# SMC_FrontPanel_ExtensionBoard_Step2_V12_.net
KiCad netlist of a schematic drawn in EAGLE
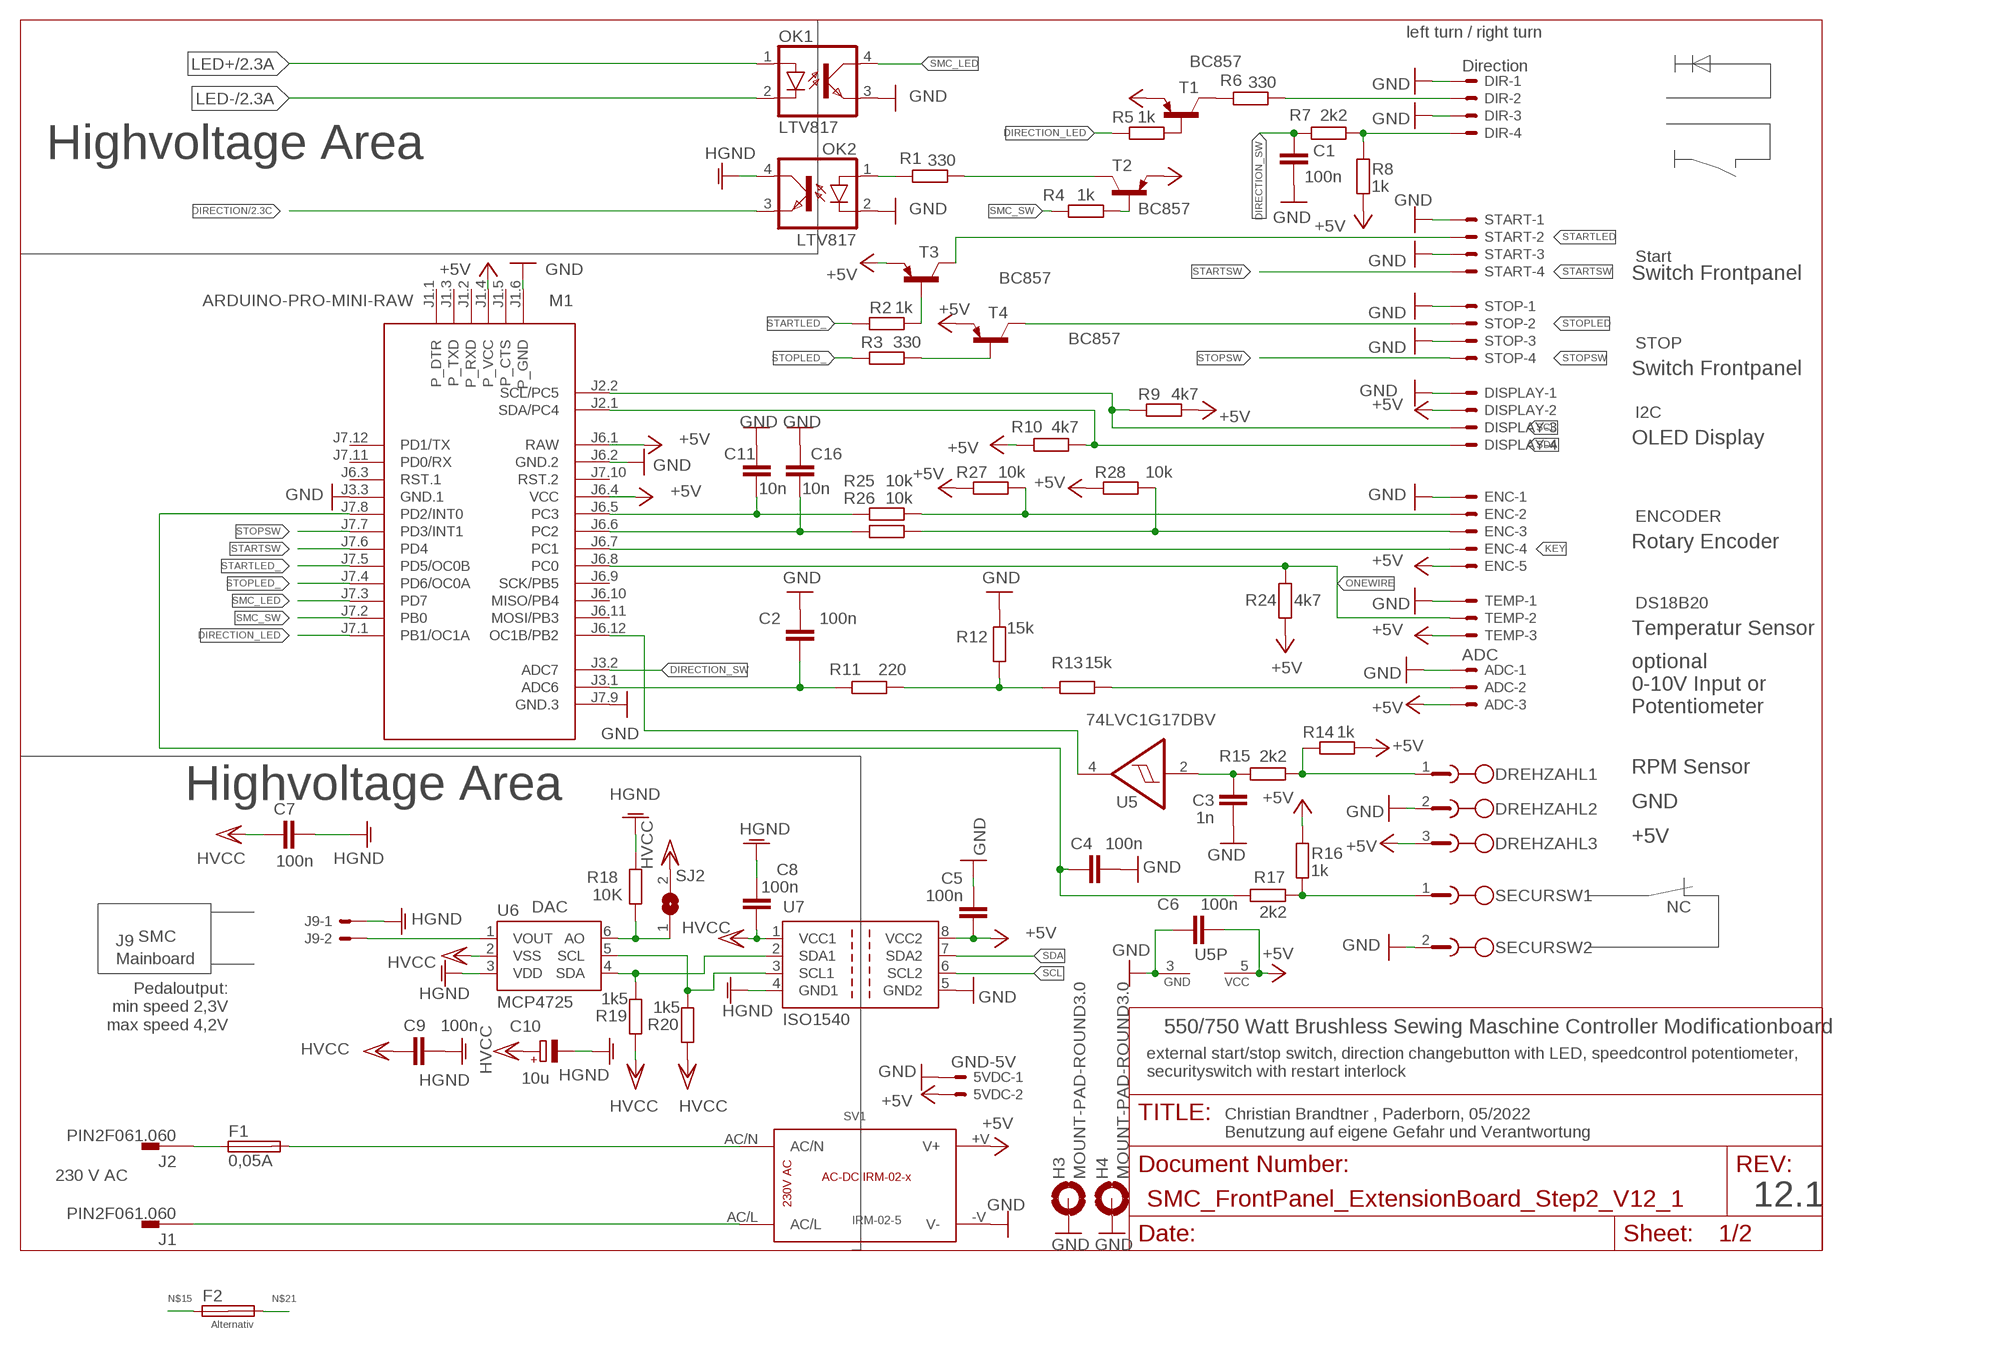
[diagram p0: schematic, sheet 1]
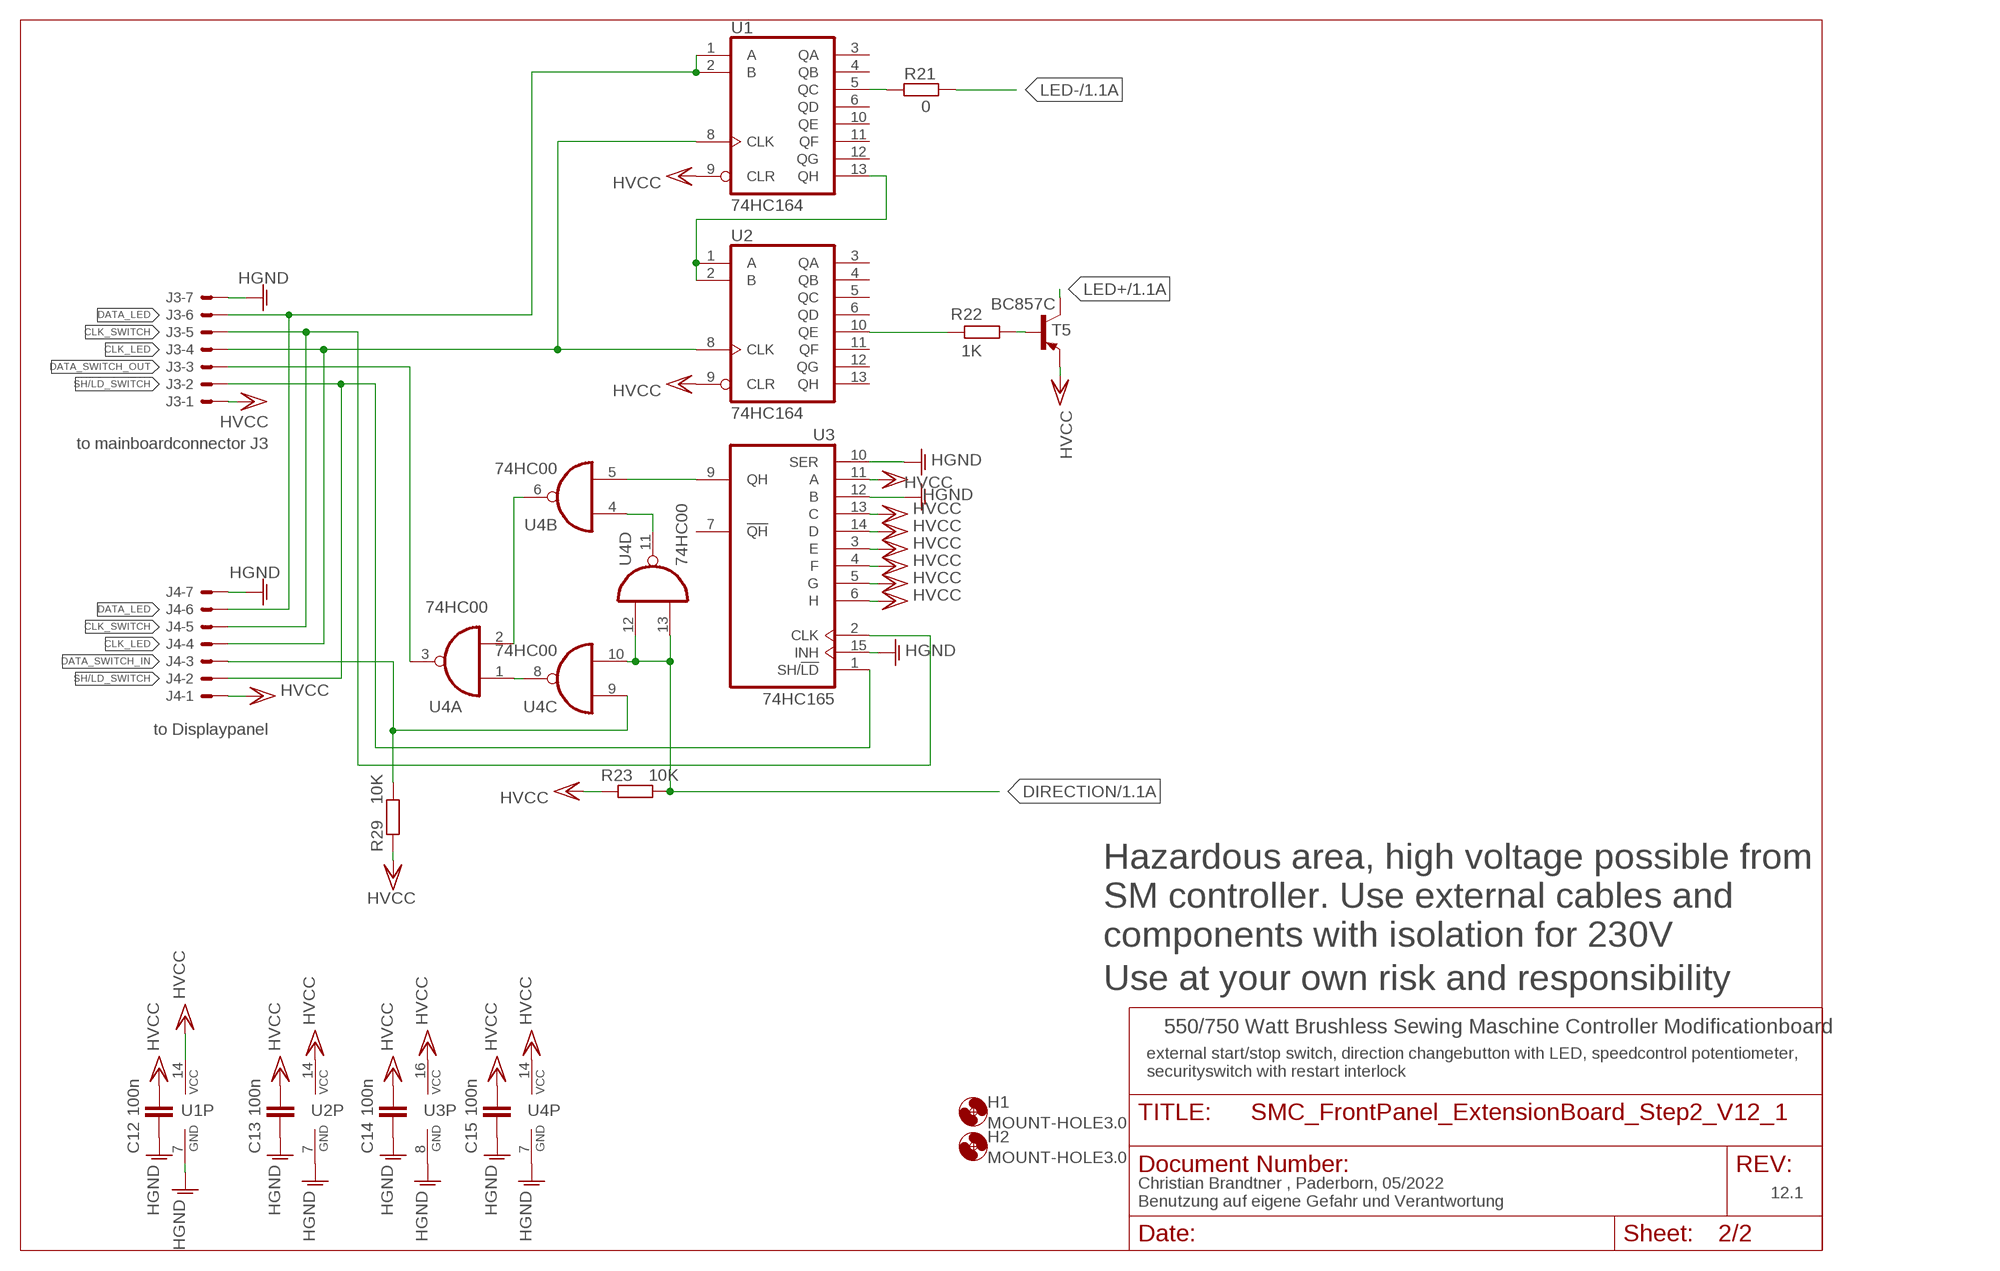
[diagram p1: schematic, sheet 2]

(export (version "E")
  (design (tool "Eeschema 10.0.6"))
  (components
    (comp (ref "5VDC")
      (value "GND-5V")
      (footprint "eagle-import:JST-XH-02-PACKAGE-ROUND-PAD")
      (libsource (lib "eagle-import") (part "JST-XH-02-PIN-ROUND-PAD"))
    )
    (comp (ref "ADC")
      (value "ADC")
      (footprint "eagle-import:JST-XH-03-PACKAGE-ROUND-PAD")
      (libsource (lib "eagle-import") (part "JST-XH-03-PIN-ROUND-PAD"))
    )
    (comp (ref "C1")
      (value "100n")
      (footprint "eagle-import:C0805")
      (libsource (lib "eagle-import") (part "C-EUC0805"))
    )
    (comp (ref "C2")
      (value "100n")
      (footprint "eagle-import:C0805")
      (libsource (lib "eagle-import") (part "C-EUC0805"))
    )
    (comp (ref "C3")
      (value "1n")
      (footprint "eagle-import:C0805")
      (libsource (lib "eagle-import") (part "C-EUC0805"))
    )
    (comp (ref "C4")
      (value "100n")
      (footprint "eagle-import:C0805")
      (libsource (lib "eagle-import") (part "C-EUC0805"))
    )
    (comp (ref "C5")
      (value "100n")
      (footprint "eagle-import:C0805")
      (libsource (lib "eagle-import") (part "C-EUC0805"))
    )
    (comp (ref "C6")
      (value "100n")
      (footprint "eagle-import:C0805")
      (libsource (lib "eagle-import") (part "C-EUC0805"))
    )
    (comp (ref "C7")
      (value "100n")
      (footprint "eagle-import:C0805")
      (libsource (lib "eagle-import") (part "C-EUC0805"))
    )
    (comp (ref "C8")
      (value "100n")
      (footprint "eagle-import:C0805")
      (libsource (lib "eagle-import") (part "C-EUC0805"))
    )
    (comp (ref "C9")
      (value "100n")
      (footprint "eagle-import:C0805")
      (libsource (lib "eagle-import") (part "C-EUC0805"))
    )
    (comp (ref "C10")
      (value "10u")
      (footprint "eagle-import:153CLV-0405")
      (libsource (lib "eagle-import") (part "CPOL-EU153CLV-0405"))
    )
    (comp (ref "C11")
      (value "10n")
      (footprint "eagle-import:C0805")
      (libsource (lib "eagle-import") (part "C-EUC0805"))
    )
    (comp (ref "C16")
      (value "10n")
      (footprint "eagle-import:C0805")
      (libsource (lib "eagle-import") (part "C-EUC0805"))
    )
    (comp (ref "DIR")
      (value "Direction")
      (footprint "eagle-import:JST-XH-04-PACKAGE-ROUND-PAD")
      (libsource (lib "eagle-import") (part "JST-XH-04-PIN-ROUND-PAD"))
    )
    (comp (ref "DISPLAY")
      (value "I2C")
      (footprint "eagle-import:JST-XH-04-PACKAGE-ROUND-PAD")
      (libsource (lib "eagle-import") (part "JST-XH-04-PIN-ROUND-PAD"))
    )
    (comp (ref "DREHZAHL")
      (value "MCV_1.5/3/-G-3.5")
      (footprint "eagle-import:1843619")
      (libsource (lib "eagle-import") (part "MCV_1.5/3/-G-3.5"))
    )
    (comp (ref "ENC")
      (value "ENCODER")
      (footprint "eagle-import:JST-XH-05-PACKAGE-ROUND-PAD")
      (libsource (lib "eagle-import") (part "JST-XH-05-PIN-ROUND-PAD"))
    )
    (comp (ref "F1")
      (value "0,05A")
      (footprint "eagle-import:MTA501100")
      (libsource (lib "eagle-import") (part "FUSE"))
    )
    (comp (ref "F2")
      (value "SHK20L")
      (footprint "eagle-import:SHK20L")
      (libsource (lib "eagle-import") (part "SHK20L"))
    )
    (comp (ref "H3")
      (value "MOUNT-PAD-ROUND3.0")
      (footprint "eagle-import:3,0-PAD")
      (libsource (lib "eagle-import") (part "MOUNT-PAD-ROUND3.0"))
    )
    (comp (ref "H4")
      (value "MOUNT-PAD-ROUND3.0")
      (footprint "eagle-import:3,0-PAD")
      (libsource (lib "eagle-import") (part "MOUNT-PAD-ROUND3.0"))
    )
    (comp (ref "J1")
      (value "PIN2F061.060")
      (footprint "eagle-import:F061.060")
      (libsource (lib "eagle-import") (part "PIN2F061.060"))
    )
    (comp (ref "J2")
      (value "PIN2F061.060")
      (footprint "eagle-import:F061.060")
      (libsource (lib "eagle-import") (part "PIN2F061.060"))
    )
    (comp (ref "J9")
      (value "JST-XH-02-PIN-ROUND-PAD")
      (footprint "eagle-import:JST-XH-02-PACKAGE-ROUND-PAD")
      (libsource (lib "eagle-import") (part "JST-XH-02-PIN-ROUND-PAD"))
    )
    (comp (ref "M1")
      (value "ARDUINO-PRO-MINI-RAW")
      (footprint "eagle-import:ARDUINO-PRO-MINI")
      (libsource (lib "eagle-import") (part "ARDUINO-PRO-MINI-RAW"))
    )
    (comp (ref "OK1")
      (value "LTV817")
      (footprint "eagle-import:SMD4-7")
      (fields (field (name "MF") "VISHAY/TELEFUNKEN") (field (name "MPN") "SFH6186-2"))
      (libsource (lib "eagle-import") (part "SFH618?6-2"))
    )
    (comp (ref "OK2")
      (value "LTV817")
      (footprint "eagle-import:SMD4-7")
      (fields (field (name "MF") "VISHAY/TELEFUNKEN") (field (name "MPN") "SFH6186-2"))
      (libsource (lib "eagle-import") (part "SFH618?6-2"))
    )
    (comp (ref "R1")
      (value "330")
      (footprint "eagle-import:R0805")
      (libsource (lib "eagle-import") (part "R-EU_R0805"))
    )
    (comp (ref "R2")
      (value "1k")
      (footprint "eagle-import:R0805")
      (libsource (lib "eagle-import") (part "R-EU_R0805"))
    )
    (comp (ref "R3")
      (value "330")
      (footprint "eagle-import:R0805")
      (libsource (lib "eagle-import") (part "R-EU_R0805"))
    )
    (comp (ref "R4")
      (value "1k")
      (footprint "eagle-import:R0805")
      (libsource (lib "eagle-import") (part "R-EU_R0805"))
    )
    (comp (ref "R5")
      (value "1k")
      (footprint "eagle-import:R0805")
      (libsource (lib "eagle-import") (part "R-EU_R0805"))
    )
    (comp (ref "R6")
      (value "330")
      (footprint "eagle-import:R0805")
      (libsource (lib "eagle-import") (part "R-EU_R0805"))
    )
    (comp (ref "R7")
      (value "2k2")
      (footprint "eagle-import:R0805")
      (libsource (lib "eagle-import") (part "R-EU_R0805"))
    )
    (comp (ref "R8")
      (value "1k")
      (footprint "eagle-import:R0805")
      (libsource (lib "eagle-import") (part "R-EU_R0805"))
    )
    (comp (ref "R9")
      (value "4k7")
      (footprint "eagle-import:R0805")
      (libsource (lib "eagle-import") (part "R-EU_R0805"))
    )
    (comp (ref "R10")
      (value "4k7")
      (footprint "eagle-import:R0805")
      (libsource (lib "eagle-import") (part "R-EU_R0805"))
    )
    (comp (ref "R11")
      (value "220")
      (footprint "eagle-import:R0805")
      (libsource (lib "eagle-import") (part "R-EU_R0805"))
    )
    (comp (ref "R12")
      (value "15k")
      (footprint "eagle-import:R0805")
      (libsource (lib "eagle-import") (part "R-EU_R0805"))
    )
    (comp (ref "R13")
      (value "15k")
      (footprint "eagle-import:R0805")
      (libsource (lib "eagle-import") (part "R-EU_R0805"))
    )
    (comp (ref "R14")
      (value "1k")
      (footprint "eagle-import:R0805")
      (libsource (lib "eagle-import") (part "R-EU_R0805"))
    )
    (comp (ref "R15")
      (value "2k2")
      (footprint "eagle-import:R0805")
      (libsource (lib "eagle-import") (part "R-EU_R0805"))
    )
    (comp (ref "R16")
      (value "1k")
      (footprint "eagle-import:R0805")
      (libsource (lib "eagle-import") (part "R-EU_R0805"))
    )
    (comp (ref "R17")
      (value "2k2")
      (footprint "eagle-import:R0805")
      (libsource (lib "eagle-import") (part "R-EU_R0805"))
    )
    (comp (ref "R18")
      (value "10K")
      (footprint "eagle-import:R0805")
      (libsource (lib "eagle-import") (part "R-EU_R0805"))
    )
    (comp (ref "R19")
      (value "1k5")
      (footprint "eagle-import:R0805")
      (libsource (lib "eagle-import") (part "R-EU_R0805"))
    )
    (comp (ref "R20")
      (value "1k5")
      (footprint "eagle-import:R0805")
      (libsource (lib "eagle-import") (part "R-EU_R0805"))
    )
    (comp (ref "R24")
      (value "4k7")
      (footprint "eagle-import:R0805")
      (libsource (lib "eagle-import") (part "R-EU_R0805"))
    )
    (comp (ref "R25")
      (value "10k")
      (footprint "eagle-import:R0805")
      (libsource (lib "eagle-import") (part "R-EU_R0805"))
    )
    (comp (ref "R26")
      (value "10k")
      (footprint "eagle-import:R0805")
      (libsource (lib "eagle-import") (part "R-EU_R0805"))
    )
    (comp (ref "R27")
      (value "10k")
      (footprint "eagle-import:R0805")
      (libsource (lib "eagle-import") (part "R-EU_R0805"))
    )
    (comp (ref "R28")
      (value "10k")
      (footprint "eagle-import:R0805")
      (libsource (lib "eagle-import") (part "R-EU_R0805"))
    )
    (comp (ref "SECURSW")
      (value "MCV_1,5/2-G-3,5")
      (footprint "eagle-import:1843606")
      (libsource (lib "eagle-import") (part "MCV_1,5/2-G-3,5"))
    )
    (comp (ref "SJ2") (value "SJ") (footprint "eagle-import:SJ") (libsource (lib "eagle-import") (part "SJ")))
    (comp (ref "START")
      (value "Start")
      (footprint "eagle-import:JST-XH-04-PACKAGE-ROUND-PAD")
      (libsource (lib "eagle-import") (part "JST-XH-04-PIN-ROUND-PAD"))
    )
    (comp (ref "STOP")
      (value "STOP")
      (footprint "eagle-import:JST-XH-04-PACKAGE-ROUND-PAD")
      (libsource (lib "eagle-import") (part "JST-XH-04-PIN-ROUND-PAD"))
    )
    (comp (ref "SV1")
      (value "IRM-02-5")
      (footprint "eagle-import:IRM-02-X")
      (libsource (lib "eagle-import") (part "IRM-02-X"))
    )
    (comp (ref "T1")
      (value "BC857")
      (footprint "eagle-import:SOT23-BEC")
      (libsource (lib "eagle-import") (part "BC857SMDA"))
    )
    (comp (ref "T2")
      (value "BC857")
      (footprint "eagle-import:SOT23-BEC")
      (libsource (lib "eagle-import") (part "BC857SMDA"))
    )
    (comp (ref "T3")
      (value "BC857")
      (footprint "eagle-import:SOT23-BEC")
      (libsource (lib "eagle-import") (part "BC857SMDA"))
    )
    (comp (ref "T4")
      (value "BC857")
      (footprint "eagle-import:SOT23-BEC")
      (libsource (lib "eagle-import") (part "BC857SMDA"))
    )
    (comp (ref "TEMP")
      (value "DS18B20")
      (footprint "eagle-import:JST-XH-03-PACKAGE-ROUND-PAD")
      (libsource (lib "eagle-import") (part "JST-XH-03-PIN-ROUND-PAD"))
    )
    (comp (ref "U5")
      (value "74LVC1G17DBV")
      (footprint "eagle-import:SOT23-5")
      (libsource (lib "eagle-import") (part "741G17DBVLVC"))
    )
    (comp (ref "U6")
      (value "MCP4725")
      (footprint "eagle-import:SOT23-6")
      (libsource (lib "eagle-import") (part "MCP4725SOT-23"))
    )
    (comp (ref "U7")
      (value "ISO1540")
      (footprint "eagle-import:SO-08")
      (libsource (lib "eagle-import") (part "ISO1540"))
    )
    (comp (ref "C12")
      (value "100n")
      (footprint "eagle-import:C0805")
      (libsource (lib "eagle-import") (part "C-EUC0805"))
    )
    (comp (ref "C13")
      (value "100n")
      (footprint "eagle-import:C0805")
      (libsource (lib "eagle-import") (part "C-EUC0805"))
    )
    (comp (ref "C14")
      (value "100n")
      (footprint "eagle-import:C0805")
      (libsource (lib "eagle-import") (part "C-EUC0805"))
    )
    (comp (ref "C15")
      (value "100n")
      (footprint "eagle-import:C0805")
      (libsource (lib "eagle-import") (part "C-EUC0805"))
    )
    (comp (ref "H1")
      (value "MOUNT-HOLE3.0")
      (footprint "eagle-import:3,0")
      (libsource (lib "eagle-import") (part "MOUNT-HOLE3.0"))
    )
    (comp (ref "H2")
      (value "MOUNT-HOLE3.0")
      (footprint "eagle-import:3,0")
      (libsource (lib "eagle-import") (part "MOUNT-HOLE3.0"))
    )
    (comp (ref "J3")
      (value "to mainboardconnector J3")
      (footprint "eagle-import:JST-XH-07-PACKAGE-ROUND-PAD")
      (libsource (lib "eagle-import") (part "JST-XH-07-PIN-ROUND-PAD"))
    )
    (comp (ref "J4")
      (value "to Displaypanel")
      (footprint "eagle-import:JST-XH-07-PACKAGE-ROUND-PAD")
      (libsource (lib "eagle-import") (part "JST-XH-07-PIN-ROUND-PAD"))
    )
    (comp (ref "R21")
      (value "0")
      (footprint "eagle-import:R0805")
      (libsource (lib "eagle-import") (part "R-EU_R0805"))
    )
    (comp (ref "R22")
      (value "1K")
      (footprint "eagle-import:R0805")
      (libsource (lib "eagle-import") (part "R-EU_R0805"))
    )
    (comp (ref "R23")
      (value "10K")
      (footprint "eagle-import:R0805")
      (libsource (lib "eagle-import") (part "R-EU_R0805"))
    )
    (comp (ref "R29")
      (value "10K")
      (footprint "eagle-import:R0805")
      (libsource (lib "eagle-import") (part "R-EU_R0805"))
    )
    (comp (ref "T5")
      (value "BC857C")
      (footprint "eagle-import:SOT23-BEC")
      (libsource (lib "eagle-import") (part "-PNP-SOT23-BECBC857C"))
    )
    (comp (ref "U1")
      (value "74HC164")
      (footprint "eagle-import:SO14")
      (libsource (lib "eagle-import") (part "74164DHC"))
    )
    (comp (ref "U2")
      (value "74HC164")
      (footprint "eagle-import:SO14")
      (libsource (lib "eagle-import") (part "74164DHC"))
    )
    (comp (ref "U3")
      (value "74HC165")
      (footprint "eagle-import:SO16")
      (libsource (lib "eagle-import") (part "74165DHC"))
    )
    (comp (ref "U4")
      (value "74HC00")
      (footprint "eagle-import:SO14")
      (libsource (lib "eagle-import") (part "7400DHC"))
    )
  )
  (nets
    (net (code "1") (name "+5V") (class "Default")
      (node (ref "5VDC") (pin "2") (pinfunction "S_2") (pintype "passive"))
      (node (ref "ADC") (pin "3") (pinfunction "S_3") (pintype "passive"))
      (node (ref "C5") (pin "1") (pinfunction "1_1") (pintype "passive"))
      (node (ref "C6") (pin "1") (pinfunction "1_1") (pintype "passive"))
      (node (ref "DISPLAY") (pin "2") (pinfunction "S_2") (pintype "passive"))
      (node (ref "DREHZAHL") (pin "3") (pinfunction "1_3") (pintype "passive"))
      (node (ref "ENC") (pin "5") (pinfunction "S_5") (pintype "passive"))
      (node (ref "M1") (pin "J1.4") (pinfunction "P_VCC_J1.4") (pintype "bidirectional"))
      (node (ref "M1") (pin "J6.1") (pinfunction "RAW_J6.1") (pintype "power_in"))
      (node (ref "M1") (pin "J6.4") (pinfunction "VCC_J6.4") (pintype "power_in"))
      (node (ref "R10") (pin "1") (pinfunction "1_1") (pintype "passive"))
      (node (ref "R14") (pin "1") (pinfunction "1_1") (pintype "passive"))
      (node (ref "R16") (pin "1") (pinfunction "1_1") (pintype "passive"))
      (node (ref "R24") (pin "2") (pinfunction "2_2") (pintype "passive"))
      (node (ref "R27") (pin "1") (pinfunction "1_1") (pintype "passive"))
      (node (ref "R28") (pin "1") (pinfunction "1_1") (pintype "passive"))
      (node (ref "R8") (pin "2") (pinfunction "2_2") (pintype "passive"))
      (node (ref "R9") (pin "1") (pinfunction "1_1") (pintype "passive"))
      (node (ref "SV1") (pin "+V") (pinfunction "V+_+V") (pintype "bidirectional"))
      (node (ref "T1") (pin "E") (pinfunction "E_E") (pintype "passive"))
      (node (ref "T2") (pin "E") (pinfunction "E_E") (pintype "passive"))
      (node (ref "T3") (pin "E") (pinfunction "E_E") (pintype "passive"))
      (node (ref "T4") (pin "E") (pinfunction "E_E") (pintype "passive"))
      (node (ref "TEMP") (pin "3") (pinfunction "S_3") (pintype "passive"))
      (node (ref "U5") (pin "5") (pinfunction "VCC_5") (pintype "power_in"))
      (node (ref "U7") (pin "8") (pinfunction "VCC2_8") (pintype "power_in"))
    )
    (net (code "2") (name "CLK_LED") (class "Default")
      (node (ref "J3") (pin "4") (pinfunction "S_4") (pintype "passive"))
      (node (ref "J4") (pin "4") (pinfunction "S_4") (pintype "passive"))
      (node (ref "U1") (pin "8") (pinfunction "CLK_8") (pintype "input"))
      (node (ref "U2") (pin "8") (pinfunction "CLK_8") (pintype "input"))
    )
    (net (code "3") (name "CLK_SWITCH") (class "Default")
      (node (ref "J3") (pin "5") (pinfunction "S_5") (pintype "passive"))
      (node (ref "J4") (pin "5") (pinfunction "S_5") (pintype "passive"))
      (node (ref "U3") (pin "2") (pinfunction "CLK_2") (pintype "input"))
    )
    (net (code "4") (name "DATA_LED") (class "Default")
      (node (ref "J3") (pin "6") (pinfunction "S_6") (pintype "passive"))
      (node (ref "J4") (pin "6") (pinfunction "S_6") (pintype "passive"))
      (node (ref "U1") (pin "1") (pinfunction "A_1") (pintype "input"))
      (node (ref "U1") (pin "2") (pinfunction "B_2") (pintype "input"))
    )
    (net (code "5") (name "DATA_SWITCH_IN") (class "Default")
      (node (ref "J4") (pin "3") (pinfunction "S_3") (pintype "passive"))
      (node (ref "R29") (pin "1") (pinfunction "1_1") (pintype "passive"))
      (node (ref "U4") (pin "9") (pinfunction "I0_9") (pintype "input"))
    )
    (net (code "6") (name "DATA_SWITCH_OUT") (class "Default")
      (node (ref "J3") (pin "3") (pinfunction "S_3") (pintype "passive"))
      (node (ref "U4") (pin "3") (pinfunction "O_3") (pintype "output"))
    )
    (net (code "7") (name "DIRECTION") (class "Default")
      (node (ref "OK2") (pin "3") (pinfunction "EMIT_3") (pintype "passive"))
      (node (ref "R23") (pin "1") (pinfunction "1_1") (pintype "passive"))
      (node (ref "U4") (pin "10") (pinfunction "I1_10") (pintype "input"))
      (node (ref "U4") (pin "12") (pinfunction "I0_12") (pintype "input"))
      (node (ref "U4") (pin "13") (pinfunction "I1_13") (pintype "input"))
    )
    (net (code "8") (name "DIRECTION_LED") (class "Default")
      (node (ref "M1") (pin "J7.1") (pinfunction "PB1/OC1A_J7.1") (pintype "bidirectional"))
      (node (ref "R5") (pin "2") (pinfunction "2_2") (pintype "passive"))
    )
    (net (code "9") (name "DIRECTION_SW") (class "Default")
      (node (ref "C1") (pin "2") (pinfunction "2_2") (pintype "passive"))
      (node (ref "M1") (pin "J3.2") (pinfunction "ADC7_J3.2") (pintype "bidirectional"))
      (node (ref "R7") (pin "1") (pinfunction "1_1") (pintype "passive"))
    )
    (net (code "10") (name "GND") (class "Default")
      (node (ref "5VDC") (pin "1") (pinfunction "S_1") (pintype "passive"))
      (node (ref "ADC") (pin "1") (pinfunction "S_1") (pintype "passive"))
      (node (ref "C1") (pin "1") (pinfunction "1_1") (pintype "passive"))
      (node (ref "C11") (pin "2") (pinfunction "2_2") (pintype "passive"))
      (node (ref "C16") (pin "2") (pinfunction "2_2") (pintype "passive"))
      (node (ref "C2") (pin "2") (pinfunction "2_2") (pintype "passive"))
      (node (ref "C3") (pin "1") (pinfunction "1_1") (pintype "passive"))
      (node (ref "C4") (pin "2") (pinfunction "2_2") (pintype "passive"))
      (node (ref "C5") (pin "2") (pinfunction "2_2") (pintype "passive"))
      (node (ref "C6") (pin "2") (pinfunction "2_2") (pintype "passive"))
      (node (ref "DIR") (pin "1") (pinfunction "S_1") (pintype "passive"))
      (node (ref "DIR") (pin "3") (pinfunction "S_3") (pintype "passive"))
      (node (ref "DISPLAY") (pin "1") (pinfunction "S_1") (pintype "passive"))
      (node (ref "DREHZAHL") (pin "2") (pinfunction "1_2") (pintype "passive"))
      (node (ref "ENC") (pin "1") (pinfunction "S_1") (pintype "passive"))
      (node (ref "H3") (pin "B3,0") (pinfunction "MOUNT_B3,0") (pintype "passive"))
      (node (ref "H4") (pin "B3,0") (pinfunction "MOUNT_B3,0") (pintype "passive"))
      (node (ref "M1") (pin "J1.6") (pinfunction "P_GND_J1.6") (pintype "bidirectional"))
      (node (ref "M1") (pin "J3.3") (pinfunction "GND.1_J3.3") (pintype "power_in"))
      (node (ref "M1") (pin "J6.2") (pinfunction "GND.2_J6.2") (pintype "power_in"))
      (node (ref "M1") (pin "J7.9") (pinfunction "GND.3_J7.9") (pintype "bidirectional"))
      (node (ref "OK1") (pin "3") (pinfunction "EMIT_3") (pintype "passive"))
      (node (ref "OK2") (pin "2") (pinfunction "C_2") (pintype "passive"))
      (node (ref "R12") (pin "2") (pinfunction "2_2") (pintype "passive"))
      (node (ref "SECURSW") (pin "2") (pinfunction "1_2") (pintype "passive"))
      (node (ref "START") (pin "1") (pinfunction "S_1") (pintype "passive"))
      (node (ref "START") (pin "3") (pinfunction "S_3") (pintype "passive"))
      (node (ref "STOP") (pin "1") (pinfunction "S_1") (pintype "passive"))
      (node (ref "STOP") (pin "3") (pinfunction "S_3") (pintype "passive"))
      (node (ref "SV1") (pin "-V") (pinfunction "V-_-V") (pintype "bidirectional"))
      (node (ref "TEMP") (pin "1") (pinfunction "S_1") (pintype "passive"))
      (node (ref "U5") (pin "3") (pinfunction "GND_3") (pintype "power_in"))
      (node (ref "U7") (pin "5") (pinfunction "GND2_5") (pintype "power_in"))
    )
    (net (code "11") (name "HGND") (class "Default")
      (node (ref "C10") (pin "-") (pinfunction "-_-") (pintype "passive"))
      (node (ref "C12") (pin "1") (pinfunction "1_1") (pintype "passive"))
      (node (ref "C13") (pin "1") (pinfunction "1_1") (pintype "passive"))
      (node (ref "C14") (pin "1") (pinfunction "1_1") (pintype "passive"))
      (node (ref "C15") (pin "1") (pinfunction "1_1") (pintype "passive"))
      (node (ref "C7") (pin "1") (pinfunction "1_1") (pintype "passive"))
      (node (ref "C8") (pin "2") (pinfunction "2_2") (pintype "passive"))
      (node (ref "C9") (pin "1") (pinfunction "1_1") (pintype "passive"))
      (node (ref "J3") (pin "7") (pinfunction "S_7") (pintype "passive"))
      (node (ref "J4") (pin "7") (pinfunction "S_7") (pintype "passive"))
      (node (ref "J9") (pin "1") (pinfunction "S_1") (pintype "passive"))
      (node (ref "OK2") (pin "4") (pinfunction "COL_4") (pintype "passive"))
      (node (ref "R18") (pin "1") (pinfunction "1_1") (pintype "passive"))
      (node (ref "U1") (pin "7") (pinfunction "GND_7") (pintype "power_in"))
      (node (ref "U2") (pin "7") (pinfunction "GND_7") (pintype "power_in"))
      (node (ref "U3") (pin "10") (pinfunction "SER_10") (pintype "input"))
      (node (ref "U3") (pin "12") (pinfunction "B_12") (pintype "input"))
      (node (ref "U3") (pin "15") (pinfunction "INH_15") (pintype "input"))
      (node (ref "U3") (pin "8") (pinfunction "GND_8") (pintype "power_in"))
      (node (ref "U4") (pin "7") (pinfunction "GND_7") (pintype "power_in"))
      (node (ref "U6") (pin "3") (pinfunction "VDD_3") (pintype "bidirectional"))
      (node (ref "U7") (pin "4") (pinfunction "GND1_4") (pintype "power_in"))
    )
    (net (code "12") (name "HVCC") (class "Default")
      (node (ref "C10") (pin "+") (pinfunction "+_+") (pintype "passive"))
      (node (ref "C12") (pin "2") (pinfunction "2_2") (pintype "passive"))
      (node (ref "C13") (pin "2") (pinfunction "2_2") (pintype "passive"))
      (node (ref "C14") (pin "2") (pinfunction "2_2") (pintype "passive"))
      (node (ref "C15") (pin "2") (pinfunction "2_2") (pintype "passive"))
      (node (ref "C7") (pin "2") (pinfunction "2_2") (pintype "passive"))
      (node (ref "C8") (pin "1") (pinfunction "1_1") (pintype "passive"))
      (node (ref "C9") (pin "2") (pinfunction "2_2") (pintype "passive"))
      (node (ref "J3") (pin "1") (pinfunction "S_1") (pintype "passive"))
      (node (ref "J4") (pin "1") (pinfunction "S_1") (pintype "passive"))
      (node (ref "R19") (pin "2") (pinfunction "2_2") (pintype "passive"))
      (node (ref "R20") (pin "2") (pinfunction "2_2") (pintype "passive"))
      (node (ref "R23") (pin "2") (pinfunction "2_2") (pintype "passive"))
      (node (ref "R29") (pin "2") (pinfunction "2_2") (pintype "passive"))
      (node (ref "SJ2") (pin "2") (pinfunction "2_2") (pintype "passive"))
      (node (ref "T5") (pin "E") (pinfunction "E_E") (pintype "passive"))
      (node (ref "U1") (pin "14") (pinfunction "VCC_14") (pintype "power_in"))
      (node (ref "U1") (pin "9") (pinfunction "CLR_9") (pintype "input"))
      (node (ref "U2") (pin "14") (pinfunction "VCC_14") (pintype "power_in"))
      (node (ref "U2") (pin "9") (pinfunction "CLR_9") (pintype "input"))
      (node (ref "U3") (pin "11") (pinfunction "A_11") (pintype "input"))
      (node (ref "U3") (pin "13") (pinfunction "C_13") (pintype "input"))
      (node (ref "U3") (pin "14") (pinfunction "D_14") (pintype "input"))
      (node (ref "U3") (pin "16") (pinfunction "VCC_16") (pintype "power_in"))
      (node (ref "U3") (pin "3") (pinfunction "E_3") (pintype "input"))
      (node (ref "U3") (pin "4") (pinfunction "F_4") (pintype "input"))
      (node (ref "U3") (pin "5") (pinfunction "G_5") (pintype "input"))
      (node (ref "U3") (pin "6") (pinfunction "H_6") (pintype "input"))
      (node (ref "U4") (pin "14") (pinfunction "VCC_14") (pintype "power_in"))
      (node (ref "U6") (pin "2") (pinfunction "VSS_2") (pintype "bidirectional"))
      (node (ref "U7") (pin "1") (pinfunction "VCC1_1") (pintype "power_in"))
    )
    (net (code "13") (name "KEY") (class "Default")
      (node (ref "ENC") (pin "4") (pinfunction "S_4") (pintype "passive"))
      (node (ref "M1") (pin "J6.7") (pinfunction "PC1_J6.7") (pintype "bidirectional"))
    )
    (net (code "14") (name "LED+") (class "Default")
      (node (ref "OK1") (pin "1") (pinfunction "A_1") (pintype "passive"))
      (node (ref "T5") (pin "C") (pinfunction "C_C") (pintype "passive"))
    )
    (net (code "15") (name "LED-") (class "Default")
      (node (ref "OK1") (pin "2") (pinfunction "C_2") (pintype "passive"))
      (node (ref "R21") (pin "2") (pinfunction "2_2") (pintype "passive"))
    )
    (net (code "16") (name "N$15") (class "Default")
      (node (ref "F1") (pin "1") (pinfunction "1_1") (pintype "passive"))
      (node (ref "F2") (pin "1A") (pinfunction "1A_1A") (pintype "passive"))
      (node (ref "J2") (pin "A1") (pinfunction "1_A1") (pintype "passive"))
      (node (ref "J2") (pin "A2") (pinfunction "1_A2") (pintype "passive"))
    )
    (net (code "17") (name "N$21") (class "Default")
      (node (ref "F1") (pin "2") (pinfunction "2_2") (pintype "passive"))
      (node (ref "F2") (pin "2A") (pinfunction "2A_2A") (pintype "passive"))
      (node (ref "SV1") (pin "AC/N") (pinfunction "AC/N_AC/N") (pintype "bidirectional"))
    )
    (net (code "18") (name "Net-(ADCB-S)") (class "Default")
      (node (ref "ADC") (pin "2") (pinfunction "S_2") (pintype "passive"))
      (node (ref "R13") (pin "1") (pinfunction "1_1") (pintype "passive"))
    )
    (net (code "19") (name "Net-(DIRB-S)") (class "Default")
      (node (ref "DIR") (pin "2") (pinfunction "S_2") (pintype "passive"))
      (node (ref "R6") (pin "1") (pinfunction "1_1") (pintype "passive"))
    )
    (net (code "20") (name "Net-(DIRD-S)") (class "Default")
      (node (ref "DIR") (pin "4") (pinfunction "S_4") (pintype "passive"))
      (node (ref "R7") (pin "2") (pinfunction "2_2") (pintype "passive"))
      (node (ref "R8") (pin "1") (pinfunction "1_1") (pintype "passive"))
    )
    (net (code "21") (name "Net-(DREHZAHL-Pad1)") (class "Default")
      (node (ref "DREHZAHL") (pin "1") (pinfunction "1_1") (pintype "passive"))
      (node (ref "R14") (pin "2") (pinfunction "2_2") (pintype "passive"))
      (node (ref "R15") (pin "2") (pinfunction "2_2") (pintype "passive"))
    )
    (net (code "22") (name "Net-(ENCB-S)") (class "Default")
      (node (ref "ENC") (pin "2") (pinfunction "S_2") (pintype "passive"))
      (node (ref "R25") (pin "2") (pinfunction "2_2") (pintype "passive"))
      (node (ref "R27") (pin "2") (pinfunction "2_2") (pintype "passive"))
    )
    (net (code "23") (name "Net-(ENCC-S)") (class "Default")
      (node (ref "ENC") (pin "3") (pinfunction "S_3") (pintype "passive"))
      (node (ref "R26") (pin "2") (pinfunction "2_2") (pintype "passive"))
      (node (ref "R28") (pin "2") (pinfunction "2_2") (pintype "passive"))
    )
    (net (code "24") (name "Net-(J1-1-PadA1)") (class "Default")
      (node (ref "J1") (pin "A1") (pinfunction "1_A1") (pintype "passive"))
      (node (ref "J1") (pin "A2") (pinfunction "1_A2") (pintype "passive"))
      (node (ref "SV1") (pin "AC/L") (pinfunction "AC/L_AC/L") (pintype "bidirectional"))
    )
    (net (code "25") (name "Net-(J9B-S)") (class "Default")
      (node (ref "J9") (pin "2") (pinfunction "S_2") (pintype "passive"))
      (node (ref "U6") (pin "1") (pinfunction "VOUT_1") (pintype "bidirectional"))
    )
    (net (code "26") (name "Net-(M1-ADC6)") (class "Default")
      (node (ref "C2") (pin "1") (pinfunction "1_1") (pintype "passive"))
      (node (ref "M1") (pin "J3.1") (pinfunction "ADC6_J3.1") (pintype "bidirectional"))
      (node (ref "R11") (pin "1") (pinfunction "1_1") (pintype "passive"))
    )
    (net (code "27") (name "Net-(M1-OC1B{slash}PB2)") (class "Default")
      (node (ref "M1") (pin "J6.12") (pinfunction "OC1B/PB2_J6.12") (pintype "bidirectional"))
      (node (ref "U5") (pin "4") (pinfunction "O_4") (pintype "output"))
    )
    (net (code "28") (name "Net-(M1-PC2)") (class "Default")
      (node (ref "C16") (pin "1") (pinfunction "1_1") (pintype "passive"))
      (node (ref "M1") (pin "J6.6") (pinfunction "PC2_J6.6") (pintype "bidirectional"))
      (node (ref "R26") (pin "1") (pinfunction "1_1") (pintype "passive"))
    )
    (net (code "29") (name "Net-(M1-PC3)") (class "Default")
      (node (ref "C11") (pin "1") (pinfunction "1_1") (pintype "passive"))
      (node (ref "M1") (pin "J6.5") (pinfunction "PC3_J6.5") (pintype "bidirectional"))
      (node (ref "R25") (pin "1") (pinfunction "1_1") (pintype "passive"))
    )
    (net (code "30") (name "Net-(M1-PD2{slash}INT0)") (class "Default")
      (node (ref "C4") (pin "1") (pinfunction "1_1") (pintype "passive"))
      (node (ref "M1") (pin "J7.8") (pinfunction "PD2/INT0_J7.8") (pintype "bidirectional"))
      (node (ref "R17") (pin "1") (pinfunction "1_1") (pintype "passive"))
    )
    (net (code "31") (name "Net-(OK2-A)") (class "Default")
      (node (ref "OK2") (pin "1") (pinfunction "A_1") (pintype "passive"))
      (node (ref "R1") (pin "2") (pinfunction "2_2") (pintype "passive"))
    )
    (net (code "32") (name "Net-(R1-Pad1)") (class "Default")
      (node (ref "R1") (pin "1") (pinfunction "1_1") (pintype "passive"))
      (node (ref "T2") (pin "C") (pinfunction "C_C") (pintype "passive"))
    )
    (net (code "33") (name "Net-(R2-Pad1)") (class "Default")
      (node (ref "R2") (pin "1") (pinfunction "1_1") (pintype "passive"))
      (node (ref "T3") (pin "B") (pinfunction "B_B") (pintype "passive"))
    )
    (net (code "34") (name "Net-(R3-Pad1)") (class "Default")
      (node (ref "R3") (pin "1") (pinfunction "1_1") (pintype "passive"))
      (node (ref "T4") (pin "B") (pinfunction "B_B") (pintype "passive"))
    )
    (net (code "35") (name "Net-(R4-Pad1)") (class "Default")
      (node (ref "R4") (pin "1") (pinfunction "1_1") (pintype "passive"))
      (node (ref "T2") (pin "B") (pinfunction "B_B") (pintype "passive"))
    )
    (net (code "36") (name "Net-(R5-Pad1)") (class "Default")
      (node (ref "R5") (pin "1") (pinfunction "1_1") (pintype "passive"))
      (node (ref "T1") (pin "B") (pinfunction "B_B") (pintype "passive"))
    )
    (net (code "37") (name "Net-(R6-Pad2)") (class "Default")
      (node (ref "R6") (pin "2") (pinfunction "2_2") (pintype "passive"))
      (node (ref "T1") (pin "C") (pinfunction "C_C") (pintype "passive"))
    )
    (net (code "38") (name "Net-(R11-Pad2)") (class "Default")
      (node (ref "R11") (pin "2") (pinfunction "2_2") (pintype "passive"))
      (node (ref "R12") (pin "1") (pinfunction "1_1") (pintype "passive"))
      (node (ref "R13") (pin "2") (pinfunction "2_2") (pintype "passive"))
    )
    (net (code "39") (name "Net-(R16-Pad2)") (class "Default")
      (node (ref "R16") (pin "2") (pinfunction "2_2") (pintype "passive"))
      (node (ref "R17") (pin "2") (pinfunction "2_2") (pintype "passive"))
      (node (ref "SECURSW") (pin "1") (pinfunction "1_1") (pintype "passive"))
    )
    (net (code "40") (name "Net-(R22-Pad1)") (class "Default")
      (node (ref "R22") (pin "1") (pinfunction "1_1") (pintype "passive"))
      (node (ref "T5") (pin "B") (pinfunction "B_B") (pintype "passive"))
    )
    (net (code "41") (name "Net-(U1A-QC)") (class "Default")
      (node (ref "R21") (pin "1") (pinfunction "1_1") (pintype "passive"))
      (node (ref "U1") (pin "5") (pinfunction "QC_5") (pintype "output"))
    )
    (net (code "42") (name "Net-(U1A-QH)") (class "Default")
      (node (ref "U1") (pin "13") (pinfunction "QH_13") (pintype "output"))
      (node (ref "U2") (pin "1") (pinfunction "A_1") (pintype "input"))
      (node (ref "U2") (pin "2") (pinfunction "B_2") (pintype "input"))
    )
    (net (code "43") (name "Net-(U2A-QE)") (class "Default")
      (node (ref "R22") (pin "2") (pinfunction "2_2") (pintype "passive"))
      (node (ref "U2") (pin "10") (pinfunction "QE_10") (pintype "output"))
    )
    (net (code "44") (name "Net-(U3A-QH)") (class "Default")
      (node (ref "U3") (pin "9") (pinfunction "QH_9") (pintype "output"))
      (node (ref "U4") (pin "5") (pinfunction "I1_5") (pintype "input"))
    )
    (net (code "45") (name "Net-(U4A-I0)") (class "Default")
      (node (ref "U4") (pin "1") (pinfunction "I0_1") (pintype "input"))
      (node (ref "U4") (pin "8") (pinfunction "O_8") (pintype "output"))
    )
    (net (code "46") (name "Net-(U4A-I1)") (class "Default")
      (node (ref "U4") (pin "2") (pinfunction "I1_2") (pintype "input"))
      (node (ref "U4") (pin "6") (pinfunction "O_6") (pintype "output"))
    )
    (net (code "47") (name "Net-(U4B-I0)") (class "Default")
      (node (ref "U4") (pin "11") (pinfunction "O_11") (pintype "output"))
      (node (ref "U4") (pin "4") (pinfunction "I0_4") (pintype "input"))
    )
    (net (code "48") (name "Net-(U5A-I)") (class "Default")
      (node (ref "C3") (pin "2") (pinfunction "2_2") (pintype "passive"))
      (node (ref "R15") (pin "1") (pinfunction "1_1") (pintype "passive"))
      (node (ref "U5") (pin "2") (pinfunction "I_2") (pintype "input"))
    )
    (net (code "49") (name "Net-(U6-AO)") (class "Default")
      (node (ref "R18") (pin "2") (pinfunction "2_2") (pintype "passive"))
      (node (ref "SJ2") (pin "1") (pinfunction "1_1") (pintype "passive"))
      (node (ref "U6") (pin "6") (pinfunction "AO_6") (pintype "bidirectional"))
    )
    (net (code "50") (name "Net-(U6-SCL)") (class "Default")
      (node (ref "R20") (pin "1") (pinfunction "1_1") (pintype "passive"))
      (node (ref "U6") (pin "5") (pinfunction "SCL_5") (pintype "bidirectional"))
      (node (ref "U7") (pin "3") (pinfunction "SCL1_3") (pintype "input"))
    )
    (net (code "51") (name "Net-(U6-SDA)") (class "Default")
      (node (ref "R19") (pin "1") (pinfunction "1_1") (pintype "passive"))
      (node (ref "U6") (pin "4") (pinfunction "SDA_4") (pintype "bidirectional"))
      (node (ref "U7") (pin "2") (pinfunction "SDA1_2") (pintype "input"))
    )
    (net (code "52") (name "ONEWIRE") (class "Default")
      (node (ref "M1") (pin "J6.8") (pinfunction "PC0_J6.8") (pintype "bidirectional"))
      (node (ref "R24") (pin "1") (pinfunction "1_1") (pintype "passive"))
      (node (ref "TEMP") (pin "2") (pinfunction "S_2") (pintype "passive"))
    )
    (net (code "53") (name "SCL") (class "Default")
      (node (ref "DISPLAY") (pin "3") (pinfunction "S_3") (pintype "passive"))
      (node (ref "M1") (pin "J2.2") (pinfunction "SCL/PC5_J2.2") (pintype "bidirectional"))
      (node (ref "R9") (pin "2") (pinfunction "2_2") (pintype "passive"))
      (node (ref "U7") (pin "6") (pinfunction "SCL2_6") (pintype "output"))
    )
    (net (code "54") (name "SDA") (class "Default")
      (node (ref "DISPLAY") (pin "4") (pinfunction "S_4") (pintype "passive"))
      (node (ref "M1") (pin "J2.1") (pinfunction "SDA/PC4_J2.1") (pintype "bidirectional"))
      (node (ref "R10") (pin "2") (pinfunction "2_2") (pintype "passive"))
      (node (ref "U7") (pin "7") (pinfunction "SDA2_7") (pintype "output"))
    )
    (net (code "55") (name "SH{slash}LD_SWITCH") (class "Default")
      (node (ref "J3") (pin "2") (pinfunction "S_2") (pintype "passive"))
      (node (ref "J4") (pin "2") (pinfunction "S_2") (pintype "passive"))
      (node (ref "U3") (pin "1") (pinfunction "SH/~{LD}_1") (pintype "input"))
    )
    (net (code "56") (name "SMC_LED") (class "Default")
      (node (ref "M1") (pin "J7.3") (pinfunction "PD7_J7.3") (pintype "bidirectional"))
      (node (ref "OK1") (pin "4") (pinfunction "COL_4") (pintype "passive"))
    )
    (net (code "57") (name "SMC_SW") (class "Default")
      (node (ref "M1") (pin "J7.2") (pinfunction "PB0_J7.2") (pintype "bidirectional"))
      (node (ref "R4") (pin "2") (pinfunction "2_2") (pintype "passive"))
    )
    (net (code "58") (name "STARTLED") (class "Default")
      (node (ref "START") (pin "2") (pinfunction "S_2") (pintype "passive"))
      (node (ref "T3") (pin "C") (pinfunction "C_C") (pintype "passive"))
    )
    (net (code "59") (name "STARTLED_") (class "Default")
      (node (ref "M1") (pin "J7.5") (pinfunction "PD5/OC0B_J7.5") (pintype "bidirectional"))
      (node (ref "R2") (pin "2") (pinfunction "2_2") (pintype "passive"))
    )
    (net (code "60") (name "STARTSW") (class "Default")
      (node (ref "M1") (pin "J7.6") (pinfunction "PD4_J7.6") (pintype "bidirectional"))
      (node (ref "START") (pin "4") (pinfunction "S_4") (pintype "passive"))
    )
    (net (code "61") (name "STOPLED") (class "Default")
      (node (ref "STOP") (pin "2") (pinfunction "S_2") (pintype "passive"))
      (node (ref "T4") (pin "C") (pinfunction "C_C") (pintype "passive"))
    )
    (net (code "62") (name "STOPLED_") (class "Default")
      (node (ref "M1") (pin "J7.4") (pinfunction "PD6/OC0A_J7.4") (pintype "bidirectional"))
      (node (ref "R3") (pin "2") (pinfunction "2_2") (pintype "passive"))
    )
    (net (code "63") (name "STOPSW") (class "Default")
      (node (ref "M1") (pin "J7.7") (pinfunction "PD3/INT1_J7.7") (pintype "bidirectional"))
      (node (ref "STOP") (pin "4") (pinfunction "S_4") (pintype "passive"))
    )
    (net (code "64") (name "unconnected-(F2-Pad1B)") (class "Default")
      (node (ref "F2") (pin "1B") (pinfunction "1B_1B") (pintype "passive"))
    )
    (net (code "65") (name "unconnected-(F2-Pad2B)") (class "Default")
      (node (ref "F2") (pin "2B") (pinfunction "2B_2B") (pintype "passive"))
    )
    (net (code "66") (name "unconnected-(M1-MISO{slash}PB4-PadJ6.10)") (class "Default")
      (node (ref "M1") (pin "J6.10") (pinfunction "MISO/PB4_J6.10") (pintype "bidirectional"))
    )
    (net (code "67") (name "unconnected-(M1-MOSI{slash}PB3-PadJ6.11)") (class "Default")
      (node (ref "M1") (pin "J6.11") (pinfunction "MOSI/PB3_J6.11") (pintype "bidirectional"))
    )
    (net (code "68") (name "unconnected-(M1-PD0{slash}RX-PadJ7.11)") (class "Default")
      (node (ref "M1") (pin "J7.11") (pinfunction "PD0/RX_J7.11") (pintype "bidirectional"))
    )
    (net (code "69") (name "unconnected-(M1-PD1{slash}TX-PadJ7.12)") (class "Default")
      (node (ref "M1") (pin "J7.12") (pinfunction "PD1/TX_J7.12") (pintype "bidirectional"))
    )
    (net (code "70") (name "unconnected-(M1-P_CTS-PadJ1.5)") (class "Default")
      (node (ref "M1") (pin "J1.5") (pinfunction "P_CTS_J1.5") (pintype "bidirectional"))
    )
    (net (code "71") (name "unconnected-(M1-P_DTR-PadJ1.1)") (class "Default")
      (node (ref "M1") (pin "J1.1") (pinfunction "P_DTR_J1.1") (pintype "bidirectional"))
    )
    (net (code "72") (name "unconnected-(M1-P_RXD-PadJ1.2)") (class "Default")
      (node (ref "M1") (pin "J1.2") (pinfunction "P_RXD_J1.2") (pintype "bidirectional"))
    )
    (net (code "73") (name "unconnected-(M1-P_TXD-PadJ1.3)") (class "Default")
      (node (ref "M1") (pin "J1.3") (pinfunction "P_TXD_J1.3") (pintype "bidirectional"))
    )
    (net (code "74") (name "unconnected-(M1-RST.1-PadJ6.3)") (class "Default")
      (node (ref "M1") (pin "J6.3") (pinfunction "RST.1_J6.3") (pintype "bidirectional"))
    )
    (net (code "75") (name "unconnected-(M1-RST.2-PadJ7.10)") (class "Default")
      (node (ref "M1") (pin "J7.10") (pinfunction "RST.2_J7.10") (pintype "bidirectional"))
    )
    (net (code "76") (name "unconnected-(M1-SCK{slash}PB5-PadJ6.9)") (class "Default")
      (node (ref "M1") (pin "J6.9") (pinfunction "SCK/PB5_J6.9") (pintype "bidirectional"))
    )
    (net (code "77") (name "unconnected-(U1A-QA-Pad3)") (class "Default")
      (node (ref "U1") (pin "3") (pinfunction "QA_3") (pintype "output"))
    )
    (net (code "78") (name "unconnected-(U1A-QB-Pad4)") (class "Default")
      (node (ref "U1") (pin "4") (pinfunction "QB_4") (pintype "output"))
    )
    (net (code "79") (name "unconnected-(U1A-QD-Pad6)") (class "Default")
      (node (ref "U1") (pin "6") (pinfunction "QD_6") (pintype "output"))
    )
    (net (code "80") (name "unconnected-(U1A-QE-Pad10)") (class "Default")
      (node (ref "U1") (pin "10") (pinfunction "QE_10") (pintype "output"))
    )
    (net (code "81") (name "unconnected-(U1A-QF-Pad11)") (class "Default")
      (node (ref "U1") (pin "11") (pinfunction "QF_11") (pintype "output"))
    )
    (net (code "82") (name "unconnected-(U1A-QG-Pad12)") (class "Default")
      (node (ref "U1") (pin "12") (pinfunction "QG_12") (pintype "output"))
    )
    (net (code "83") (name "unconnected-(U2A-QA-Pad3)") (class "Default")
      (node (ref "U2") (pin "3") (pinfunction "QA_3") (pintype "output"))
    )
    (net (code "84") (name "unconnected-(U2A-QB-Pad4)") (class "Default")
      (node (ref "U2") (pin "4") (pinfunction "QB_4") (pintype "output"))
    )
    (net (code "85") (name "unconnected-(U2A-QC-Pad5)") (class "Default")
      (node (ref "U2") (pin "5") (pinfunction "QC_5") (pintype "output"))
    )
    (net (code "86") (name "unconnected-(U2A-QD-Pad6)") (class "Default")
      (node (ref "U2") (pin "6") (pinfunction "QD_6") (pintype "output"))
    )
    (net (code "87") (name "unconnected-(U2A-QF-Pad11)") (class "Default")
      (node (ref "U2") (pin "11") (pinfunction "QF_11") (pintype "output"))
    )
    (net (code "88") (name "unconnected-(U2A-QG-Pad12)") (class "Default")
      (node (ref "U2") (pin "12") (pinfunction "QG_12") (pintype "output"))
    )
    (net (code "89") (name "unconnected-(U2A-QH-Pad13)") (class "Default")
      (node (ref "U2") (pin "13") (pinfunction "QH_13") (pintype "output"))
    )
    (net (code "90") (name "unconnected-(U3A-~{QH}-Pad7)") (class "Default")
      (node (ref "U3") (pin "7") (pinfunction "~{QH}_7") (pintype "output"))
    )
  )
)
